# Dialer.net
KiCad netlist of a schematic drawn in EAGLE
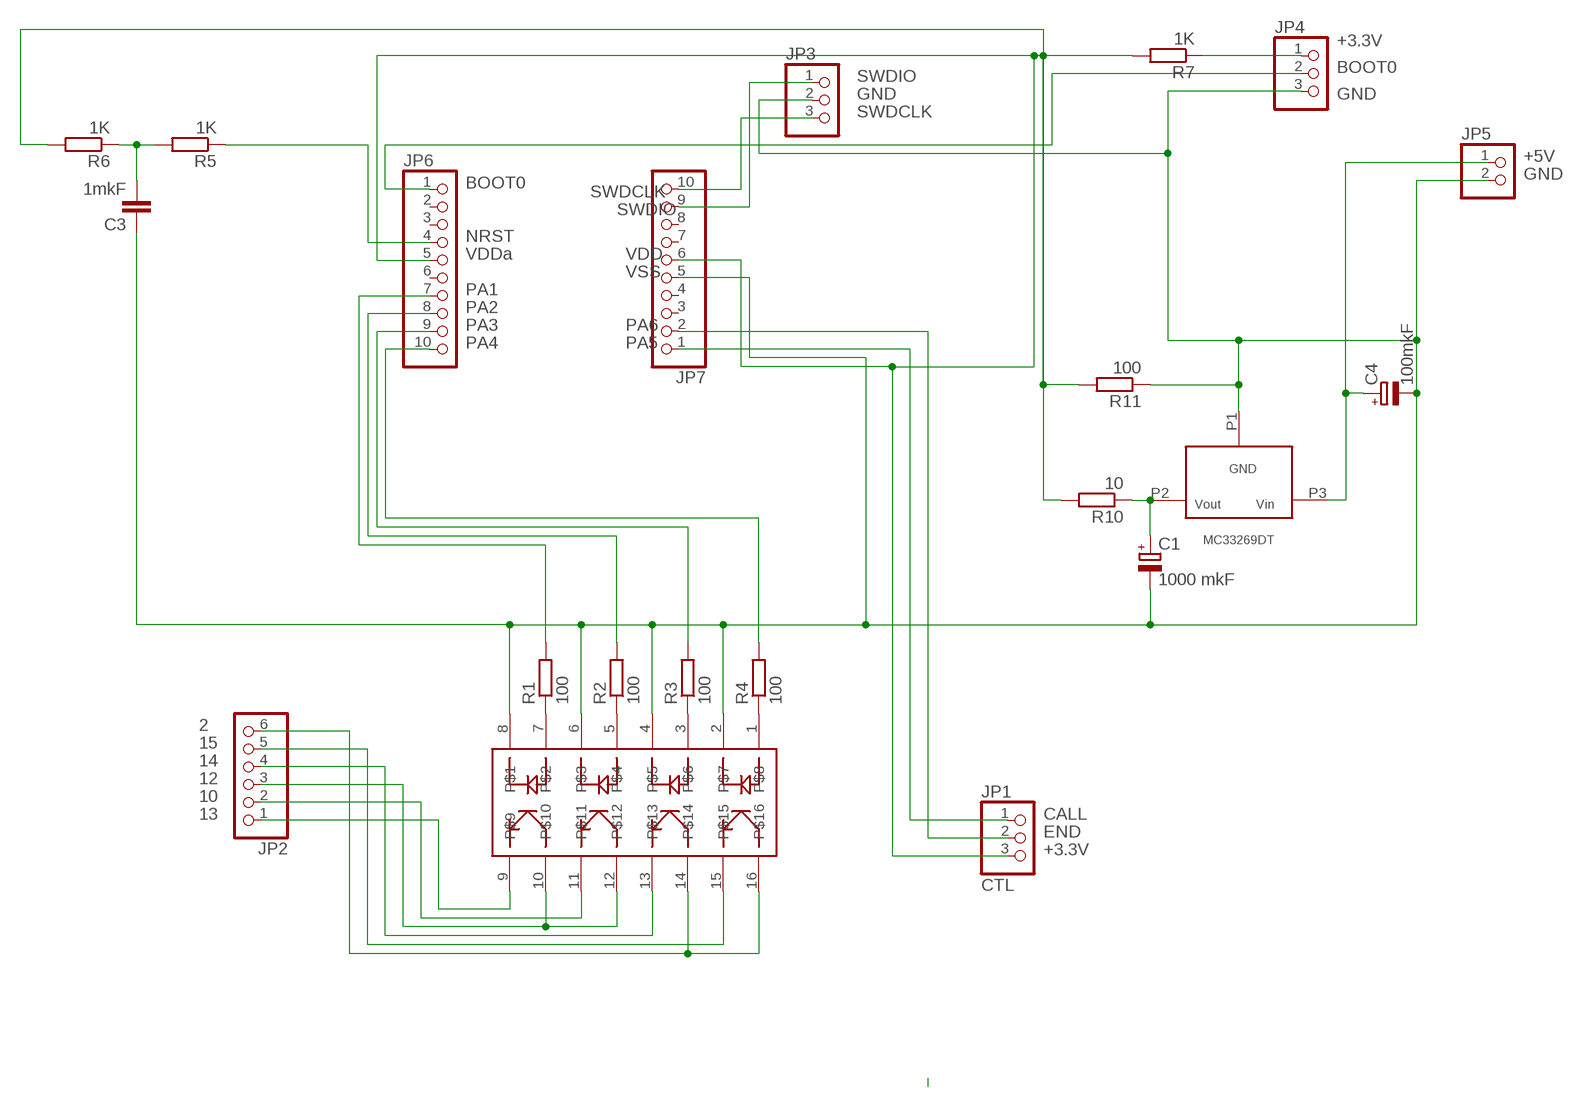
[diagram p0: schematic, sheet 1]

(export (version "E")
  (design (tool "Eeschema 10.0.6"))
  (components
    (comp (ref "C1")
      (value "1000 mkF")
      (footprint "eagle-import:E3,5-8")
      (libsource (lib "eagle-import") (part "CPOL-EUE3.5-8"))
    )
    (comp (ref "C3")
      (value "1mkF")
      (footprint "eagle-import:C1206")
      (libsource (lib "eagle-import") (part "C-EUC1206"))
    )
    (comp (ref "C4")
      (value "100mkF")
      (footprint "eagle-import:E5-6")
      (libsource (lib "eagle-import") (part "CPOL-EUE5-6"))
    )
    (comp (ref "JP1")
      (value "CTL")
      (footprint "eagle-import:1X03")
      (libsource (lib "eagle-import") (part "PINHD-1X3"))
    )
    (comp (ref "JP2")
      (value "PINHD-1X6")
      (footprint "eagle-import:1X06")
      (libsource (lib "eagle-import") (part "PINHD-1X6"))
    )
    (comp (ref "JP3")
      (value "PINHD-1X3")
      (footprint "eagle-import:1X03")
      (libsource (lib "eagle-import") (part "PINHD-1X3"))
    )
    (comp (ref "JP4")
      (value "PINHD-1X3")
      (footprint "eagle-import:1X03")
      (libsource (lib "eagle-import") (part "PINHD-1X3"))
    )
    (comp (ref "JP5")
      (value "PINHD-1X2")
      (footprint "eagle-import:1X02")
      (libsource (lib "eagle-import") (part "PINHD-1X2"))
    )
    (comp (ref "JP6")
      (value "PINHD-1X10")
      (footprint "eagle-import:1X10")
      (libsource (lib "eagle-import") (part "PINHD-1X10"))
    )
    (comp (ref "JP7")
      (value "PINHD-1X10")
      (footprint "eagle-import:1X10")
      (libsource (lib "eagle-import") (part "PINHD-1X10"))
    )
    (comp (ref "R1")
      (value "100")
      (footprint "eagle-import:M1206")
      (libsource (lib "eagle-import") (part "R-EU_M1206"))
    )
    (comp (ref "R2")
      (value "100")
      (footprint "eagle-import:M1206")
      (libsource (lib "eagle-import") (part "R-EU_M1206"))
    )
    (comp (ref "R3")
      (value "100")
      (footprint "eagle-import:M1206")
      (libsource (lib "eagle-import") (part "R-EU_M1206"))
    )
    (comp (ref "R4")
      (value "100")
      (footprint "eagle-import:M1206")
      (libsource (lib "eagle-import") (part "R-EU_M1206"))
    )
    (comp (ref "R5")
      (value "1K")
      (footprint "eagle-import:M1206")
      (libsource (lib "eagle-import") (part "R-EU_M1206"))
    )
    (comp (ref "R6")
      (value "1K")
      (footprint "eagle-import:M1206")
      (libsource (lib "eagle-import") (part "R-EU_M1206"))
    )
    (comp (ref "R7")
      (value "1K")
      (footprint "eagle-import:M1206")
      (libsource (lib "eagle-import") (part "R-EU_M1206"))
    )
    (comp (ref "R10")
      (value "10")
      (footprint "eagle-import:M1206")
      (libsource (lib "eagle-import") (part "R-EU_M1206"))
    )
    (comp (ref "R11")
      (value "100")
      (footprint "eagle-import:M1206")
      (libsource (lib "eagle-import") (part "R-EU_M1206"))
    )
    (comp (ref "U$1")
      (value "LTV847")
      (footprint "eagle-import:DIL16")
      (libsource (lib "eagle-import") (part "LTV847"))
    )
    (comp (ref "U$3")
      (value "MC33269DT")
      (footprint "eagle-import:MC33269DT")
      (libsource (lib "eagle-import") (part "MC33269DT"))
    )
  )
  (nets
    (net (code "1") (name "Net-(C3-Pad2)") (class "Default")
      (node (ref "C3") (pin "2") (pinfunction "2_2") (pintype "passive"))
      (node (ref "R5") (pin "2") (pinfunction "2_2") (pintype "passive"))
      (node (ref "R6") (pin "1") (pinfunction "1_1") (pintype "passive"))
    )
    (net (code "2") (name "Net-(JP1-Pad1)") (class "Default")
      (node (ref "JP1") (pin "1") (pinfunction "1_1") (pintype "passive"))
      (node (ref "JP7") (pin "1") (pinfunction "1_1") (pintype "passive"))
    )
    (net (code "3") (name "Net-(JP1-Pad2)") (class "Default")
      (node (ref "JP1") (pin "2") (pinfunction "2_2") (pintype "passive"))
      (node (ref "JP7") (pin "2") (pinfunction "2_2") (pintype "passive"))
    )
    (net (code "4") (name "Net-(JP1-Pad3)") (class "Default")
      (node (ref "JP1") (pin "3") (pinfunction "3_3") (pintype "passive"))
      (node (ref "JP6") (pin "5") (pinfunction "5_5") (pintype "passive"))
      (node (ref "JP7") (pin "6") (pinfunction "6_6") (pintype "passive"))
      (node (ref "R10") (pin "2") (pinfunction "2_2") (pintype "passive"))
      (node (ref "R11") (pin "2") (pinfunction "2_2") (pintype "passive"))
      (node (ref "R6") (pin "2") (pinfunction "2_2") (pintype "passive"))
      (node (ref "R7") (pin "2") (pinfunction "2_2") (pintype "passive"))
    )
    (net (code "5") (name "Net-(JP3-Pad1)") (class "Default")
      (node (ref "JP3") (pin "1") (pinfunction "1_1") (pintype "passive"))
      (node (ref "JP7") (pin "9") (pinfunction "9_9") (pintype "passive"))
    )
    (net (code "6") (name "Net-(JP3-Pad3)") (class "Default")
      (node (ref "JP3") (pin "3") (pinfunction "3_3") (pintype "passive"))
      (node (ref "JP7") (pin "10") (pinfunction "10_10") (pintype "passive"))
    )
    (net (code "7") (name "Net-(JP4-Pad1)") (class "Default")
      (node (ref "JP4") (pin "1") (pinfunction "1_1") (pintype "passive"))
      (node (ref "R7") (pin "1") (pinfunction "1_1") (pintype "passive"))
    )
    (net (code "8") (name "Net-(JP4-Pad2)") (class "Default")
      (node (ref "JP4") (pin "2") (pinfunction "2_2") (pintype "passive"))
      (node (ref "JP6") (pin "1") (pinfunction "1_1") (pintype "passive"))
    )
    (net (code "9") (name "Net-(JP6-Pad4)") (class "Default")
      (node (ref "JP6") (pin "4") (pinfunction "4_4") (pintype "passive"))
      (node (ref "R5") (pin "1") (pinfunction "1_1") (pintype "passive"))
    )
    (net (code "10") (name "Net-(JP6-Pad7)") (class "Default")
      (node (ref "JP6") (pin "7") (pinfunction "7_7") (pintype "passive"))
      (node (ref "R1") (pin "2") (pinfunction "2_2") (pintype "passive"))
    )
    (net (code "11") (name "Net-(JP6-Pad8)") (class "Default")
      (node (ref "JP6") (pin "8") (pinfunction "8_8") (pintype "passive"))
      (node (ref "R2") (pin "2") (pinfunction "2_2") (pintype "passive"))
    )
    (net (code "12") (name "Net-(JP6-Pad9)") (class "Default")
      (node (ref "JP6") (pin "9") (pinfunction "9_9") (pintype "passive"))
      (node (ref "R3") (pin "2") (pinfunction "2_2") (pintype "passive"))
    )
    (net (code "13") (name "Net-(JP6-Pad10)") (class "Default")
      (node (ref "JP6") (pin "10") (pinfunction "10_10") (pintype "passive"))
      (node (ref "R4") (pin "2") (pinfunction "2_2") (pintype "passive"))
    )
    (net (code "14") (name "Net-(U$1-P$1)") (class "Default")
      (node (ref "C1") (pin "-") (pinfunction "-_-") (pintype "passive"))
      (node (ref "C3") (pin "1") (pinfunction "1_1") (pintype "passive"))
      (node (ref "C4") (pin "-") (pinfunction "-_-") (pintype "passive"))
      (node (ref "JP3") (pin "2") (pinfunction "2_2") (pintype "passive"))
      (node (ref "JP4") (pin "3") (pinfunction "3_3") (pintype "passive"))
      (node (ref "JP5") (pin "2") (pinfunction "2_2") (pintype "passive"))
      (node (ref "JP7") (pin "5") (pinfunction "5_5") (pintype "passive"))
      (node (ref "R11") (pin "1") (pinfunction "1_1") (pintype "passive"))
      (node (ref "U$1") (pin "2") (pinfunction "P$7_2") (pintype "passive"))
      (node (ref "U$1") (pin "4") (pinfunction "P$5_4") (pintype "passive"))
      (node (ref "U$1") (pin "6") (pinfunction "P$3_6") (pintype "passive"))
      (node (ref "U$1") (pin "8") (pinfunction "P$1_8") (pintype "passive"))
      (node (ref "U$3") (pin "P1") (pinfunction "GND_P1") (pintype "power_in"))
    )
    (net (code "15") (name "Net-(U$1-P$2)") (class "Default")
      (node (ref "R1") (pin "1") (pinfunction "1_1") (pintype "passive"))
      (node (ref "U$1") (pin "7") (pinfunction "P$2_7") (pintype "passive"))
    )
    (net (code "16") (name "Net-(U$1-P$4)") (class "Default")
      (node (ref "R2") (pin "1") (pinfunction "1_1") (pintype "passive"))
      (node (ref "U$1") (pin "5") (pinfunction "P$4_5") (pintype "passive"))
    )
    (net (code "17") (name "Net-(U$1-P$6)") (class "Default")
      (node (ref "R3") (pin "1") (pinfunction "1_1") (pintype "passive"))
      (node (ref "U$1") (pin "3") (pinfunction "P$6_3") (pintype "passive"))
    )
    (net (code "18") (name "Net-(U$1-P$8)") (class "Default")
      (node (ref "R4") (pin "1") (pinfunction "1_1") (pintype "passive"))
      (node (ref "U$1") (pin "1") (pinfunction "P$8_1") (pintype "passive"))
    )
    (net (code "19") (name "Net-(U$1-P$9)") (class "Default")
      (node (ref "JP2") (pin "1") (pinfunction "1_1") (pintype "passive"))
      (node (ref "U$1") (pin "9") (pinfunction "P$9_9") (pintype "passive"))
    )
    (net (code "20") (name "Net-(U$1-P$10)") (class "Default")
      (node (ref "JP2") (pin "3") (pinfunction "3_3") (pintype "passive"))
      (node (ref "U$1") (pin "10") (pinfunction "P$10_10") (pintype "passive"))
      (node (ref "U$1") (pin "12") (pinfunction "P$12_12") (pintype "passive"))
    )
    (net (code "21") (name "Net-(U$1-P$11)") (class "Default")
      (node (ref "JP2") (pin "2") (pinfunction "2_2") (pintype "passive"))
      (node (ref "U$1") (pin "11") (pinfunction "P$11_11") (pintype "passive"))
    )
    (net (code "22") (name "Net-(U$1-P$13)") (class "Default")
      (node (ref "JP2") (pin "4") (pinfunction "4_4") (pintype "passive"))
      (node (ref "U$1") (pin "13") (pinfunction "P$13_13") (pintype "passive"))
    )
    (net (code "23") (name "Net-(U$1-P$14)") (class "Default")
      (node (ref "JP2") (pin "6") (pinfunction "6_6") (pintype "passive"))
      (node (ref "U$1") (pin "14") (pinfunction "P$14_14") (pintype "passive"))
      (node (ref "U$1") (pin "16") (pinfunction "P$16_16") (pintype "passive"))
    )
    (net (code "24") (name "Net-(U$1-P$15)") (class "Default")
      (node (ref "JP2") (pin "5") (pinfunction "5_5") (pintype "passive"))
      (node (ref "U$1") (pin "15") (pinfunction "P$15_15") (pintype "passive"))
    )
    (net (code "25") (name "Net-(U$3-VIN)") (class "Default")
      (node (ref "C4") (pin "+") (pinfunction "+_+") (pintype "passive"))
      (node (ref "JP5") (pin "1") (pinfunction "1_1") (pintype "passive"))
      (node (ref "U$3") (pin "P3") (pinfunction "VIN_P3") (pintype "input"))
    )
    (net (code "26") (name "Net-(U$3-VOUT)") (class "Default")
      (node (ref "C1") (pin "+") (pinfunction "+_+") (pintype "passive"))
      (node (ref "R10") (pin "1") (pinfunction "1_1") (pintype "passive"))
      (node (ref "U$3") (pin "P2") (pinfunction "VOUT_P2") (pintype "output"))
    )
    (net (code "27") (name "unconnected-(JP6-Pad2)") (class "Default")
      (node (ref "JP6") (pin "2") (pinfunction "2_2") (pintype "passive"))
    )
    (net (code "28") (name "unconnected-(JP6-Pad3)") (class "Default")
      (node (ref "JP6") (pin "3") (pinfunction "3_3") (pintype "passive"))
    )
    (net (code "29") (name "unconnected-(JP6-Pad6)") (class "Default")
      (node (ref "JP6") (pin "6") (pinfunction "6_6") (pintype "passive"))
    )
    (net (code "30") (name "unconnected-(JP7-Pad3)") (class "Default")
      (node (ref "JP7") (pin "3") (pinfunction "3_3") (pintype "passive"))
    )
    (net (code "31") (name "unconnected-(JP7-Pad4)") (class "Default")
      (node (ref "JP7") (pin "4") (pinfunction "4_4") (pintype "passive"))
    )
    (net (code "32") (name "unconnected-(JP7-Pad7)") (class "Default")
      (node (ref "JP7") (pin "7") (pinfunction "7_7") (pintype "passive"))
    )
    (net (code "33") (name "unconnected-(JP7-Pad8)") (class "Default")
      (node (ref "JP7") (pin "8") (pinfunction "8_8") (pintype "passive"))
    )
  )
)
